# max636.net
KiCad netlist of a schematic drawn in EAGLE
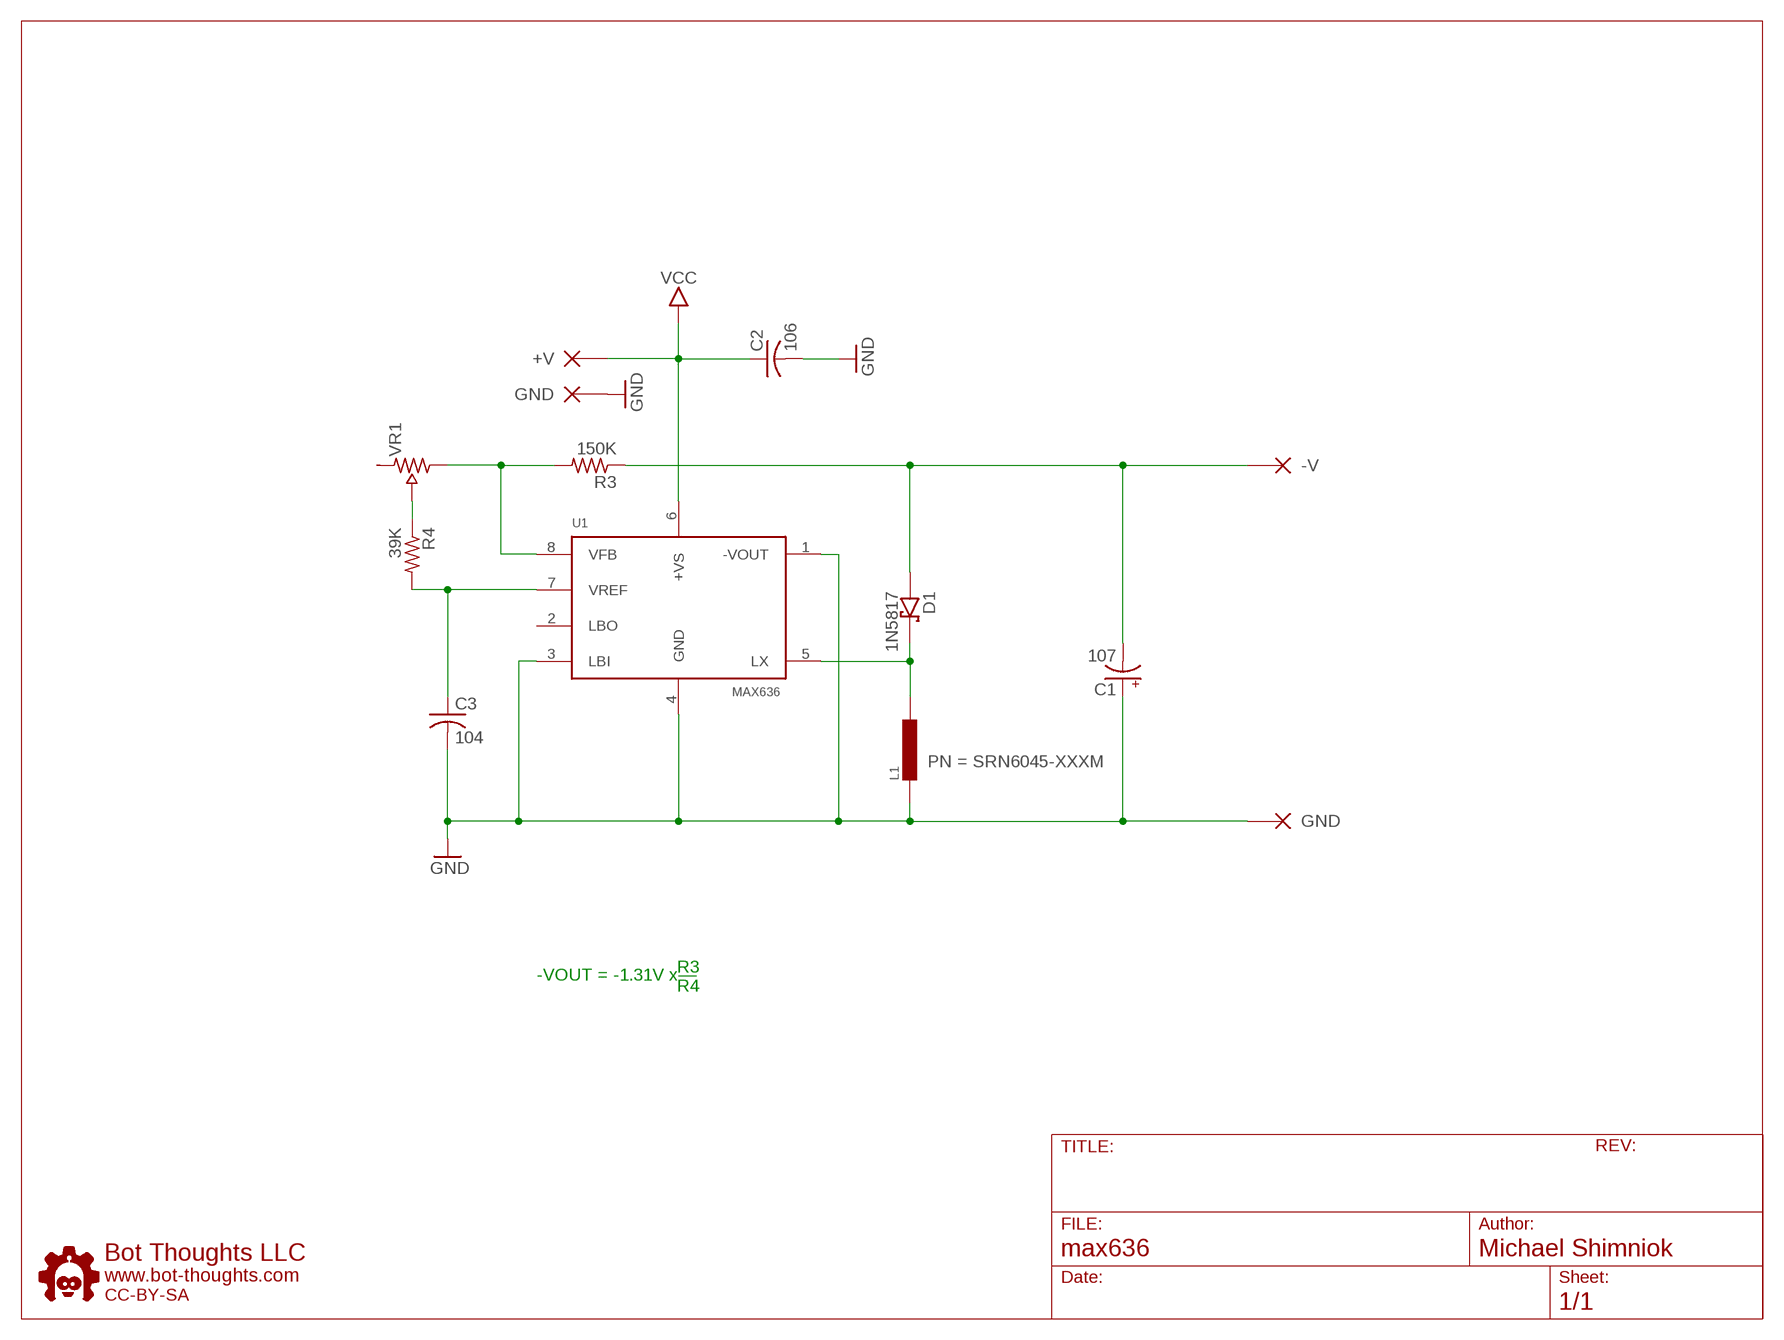
[diagram p0: schematic, sheet 1]

(export (version "E")
  (design (tool "Eeschema 10.0.6"))
  (components
    (comp (ref "C1")
      (value "107")
      (footprint "eagle-import:SMC_B")
      (libsource (lib "eagle-import") (part "CPOL_SMC_B"))
    )
    (comp (ref "C2")
      (value "106")
      (footprint "eagle-import:0603")
      (libsource (lib "eagle-import") (part "C-0603"))
    )
    (comp (ref "C3")
      (value "104")
      (footprint "eagle-import:0603")
      (libsource (lib "eagle-import") (part "C-0603"))
    )
    (comp (ref "D1")
      (value "1N5817")
      (footprint "eagle-import:SOD-323")
      (libsource (lib "eagle-import") (part "SCHOTTKY-DIODE-B5817WS-TP"))
    )
    (comp (ref "J1")
      (value "+V")
      (footprint "eagle-import:1X01-S")
      (libsource (lib "eagle-import") (part "PINHEAD-1"))
    )
    (comp (ref "J2")
      (value "-V")
      (footprint "eagle-import:1X01-S")
      (libsource (lib "eagle-import") (part "PINHEAD-1"))
    )
    (comp (ref "J3")
      (value "GND")
      (footprint "eagle-import:1X01-S")
      (libsource (lib "eagle-import") (part "PINHEAD-1"))
    )
    (comp (ref "J4")
      (value "GND")
      (footprint "eagle-import:1X01-S")
      (libsource (lib "eagle-import") (part "PINHEAD-1"))
    )
    (comp (ref "L1")
      (value "INDUCTOR-VLS6045EX")
      (footprint "eagle-import:VLS6045EX")
      (fields (field (name "PN") "SRN6045-XXXM"))
      (libsource (lib "eagle-import") (part "INDUCTOR-VLS6045EX"))
    )
    (comp (ref "R3")
      (value "150K")
      (footprint "eagle-import:0603")
      (libsource (lib "eagle-import") (part "R0603"))
    )
    (comp (ref "R4")
      (value "39K")
      (footprint "eagle-import:0603")
      (libsource (lib "eagle-import") (part "R0603"))
    )
    (comp (ref "U$1")
      (value "BTLOGO-LOGO-SM")
      (footprint "eagle-import:BTLOGOS")
      (libsource (lib "eagle-import") (part "BTLOGO-LOGO-SM"))
    )
    (comp (ref "U1")
      (value "MAX636")
      (footprint "eagle-import:PDIP8")
      (libsource (lib "eagle-import") (part "MAX636DIP"))
    )
    (comp (ref "VR1")
      (value "TRIM-PV36W")
      (footprint "eagle-import:PV36W")
      (libsource (lib "eagle-import") (part "TRIM-PV36W"))
    )
  )
  (nets
    (net (code "1") (name "GND") (class "Default")
      (node (ref "C1") (pin "+") (pinfunction "+_+") (pintype "passive"))
      (node (ref "C2") (pin "2") (pinfunction "-_2") (pintype "passive"))
      (node (ref "C3") (pin "2") (pinfunction "-_2") (pintype "passive"))
      (node (ref "J3") (pin "1") (pinfunction "P_1") (pintype "bidirectional"))
      (node (ref "J4") (pin "1") (pinfunction "P_1") (pintype "bidirectional"))
      (node (ref "L1") (pin "1") (pinfunction "1_1") (pintype "passive"))
      (node (ref "U1") (pin "1") (pinfunction "-VOUT_1") (pintype "power_in"))
      (node (ref "U1") (pin "3") (pinfunction "LBI_3") (pintype "bidirectional"))
      (node (ref "U1") (pin "4") (pinfunction "GND_4") (pintype "power_in"))
    )
    (net (code "2") (name "Net-(C3-+)") (class "Default")
      (node (ref "C3") (pin "1") (pinfunction "+_1") (pintype "passive"))
      (node (ref "R4") (pin "2") (pinfunction "2_2") (pintype "passive"))
      (node (ref "U1") (pin "7") (pinfunction "VREF_7") (pintype "bidirectional"))
    )
    (net (code "3") (name "Net-(J2-P)") (class "Default")
      (node (ref "C1") (pin "-") (pinfunction "-_-") (pintype "passive"))
      (node (ref "D1") (pin "A") (pinfunction "A_A") (pintype "passive"))
      (node (ref "J2") (pin "1") (pinfunction "P_1") (pintype "bidirectional"))
      (node (ref "R3") (pin "1") (pinfunction "1_1") (pintype "passive"))
    )
    (net (code "4") (name "Net-(U1-LX)") (class "Default")
      (node (ref "D1") (pin "C") (pinfunction "C_C") (pintype "passive"))
      (node (ref "L1") (pin "2") (pinfunction "2_2") (pintype "passive"))
      (node (ref "U1") (pin "5") (pinfunction "LX_5") (pintype "bidirectional"))
    )
    (net (code "5") (name "Net-(U1-VFB)") (class "Default")
      (node (ref "R3") (pin "2") (pinfunction "2_2") (pintype "passive"))
      (node (ref "U1") (pin "8") (pinfunction "VFB_8") (pintype "bidirectional"))
      (node (ref "VR1") (pin "1") (pinfunction "A_1") (pintype "passive"))
    )
    (net (code "6") (name "Net-(VR1-WIPER)") (class "Default")
      (node (ref "R4") (pin "1") (pinfunction "1_1") (pintype "passive"))
      (node (ref "VR1") (pin "2") (pinfunction "WIPER_2") (pintype "passive"))
    )
    (net (code "7") (name "VCC") (class "Default")
      (node (ref "C2") (pin "1") (pinfunction "+_1") (pintype "passive"))
      (node (ref "J1") (pin "1") (pinfunction "P_1") (pintype "bidirectional"))
      (node (ref "U1") (pin "6") (pinfunction "+VS_6") (pintype "power_in"))
    )
    (net (code "8") (name "unconnected-(U1-LBO-Pad2)") (class "Default")
      (node (ref "U1") (pin "2") (pinfunction "LBO_2") (pintype "bidirectional"))
    )
    (net (code "9") (name "unconnected-(VR1-B-Pad3)") (class "Default")
      (node (ref "VR1") (pin "3") (pinfunction "B_3") (pintype "passive"))
    )
  )
)
